# 5_-_Position2Go_PowerSupply_and_Connecto.net
KiCad netlist of a schematic drawn in Altium Designer
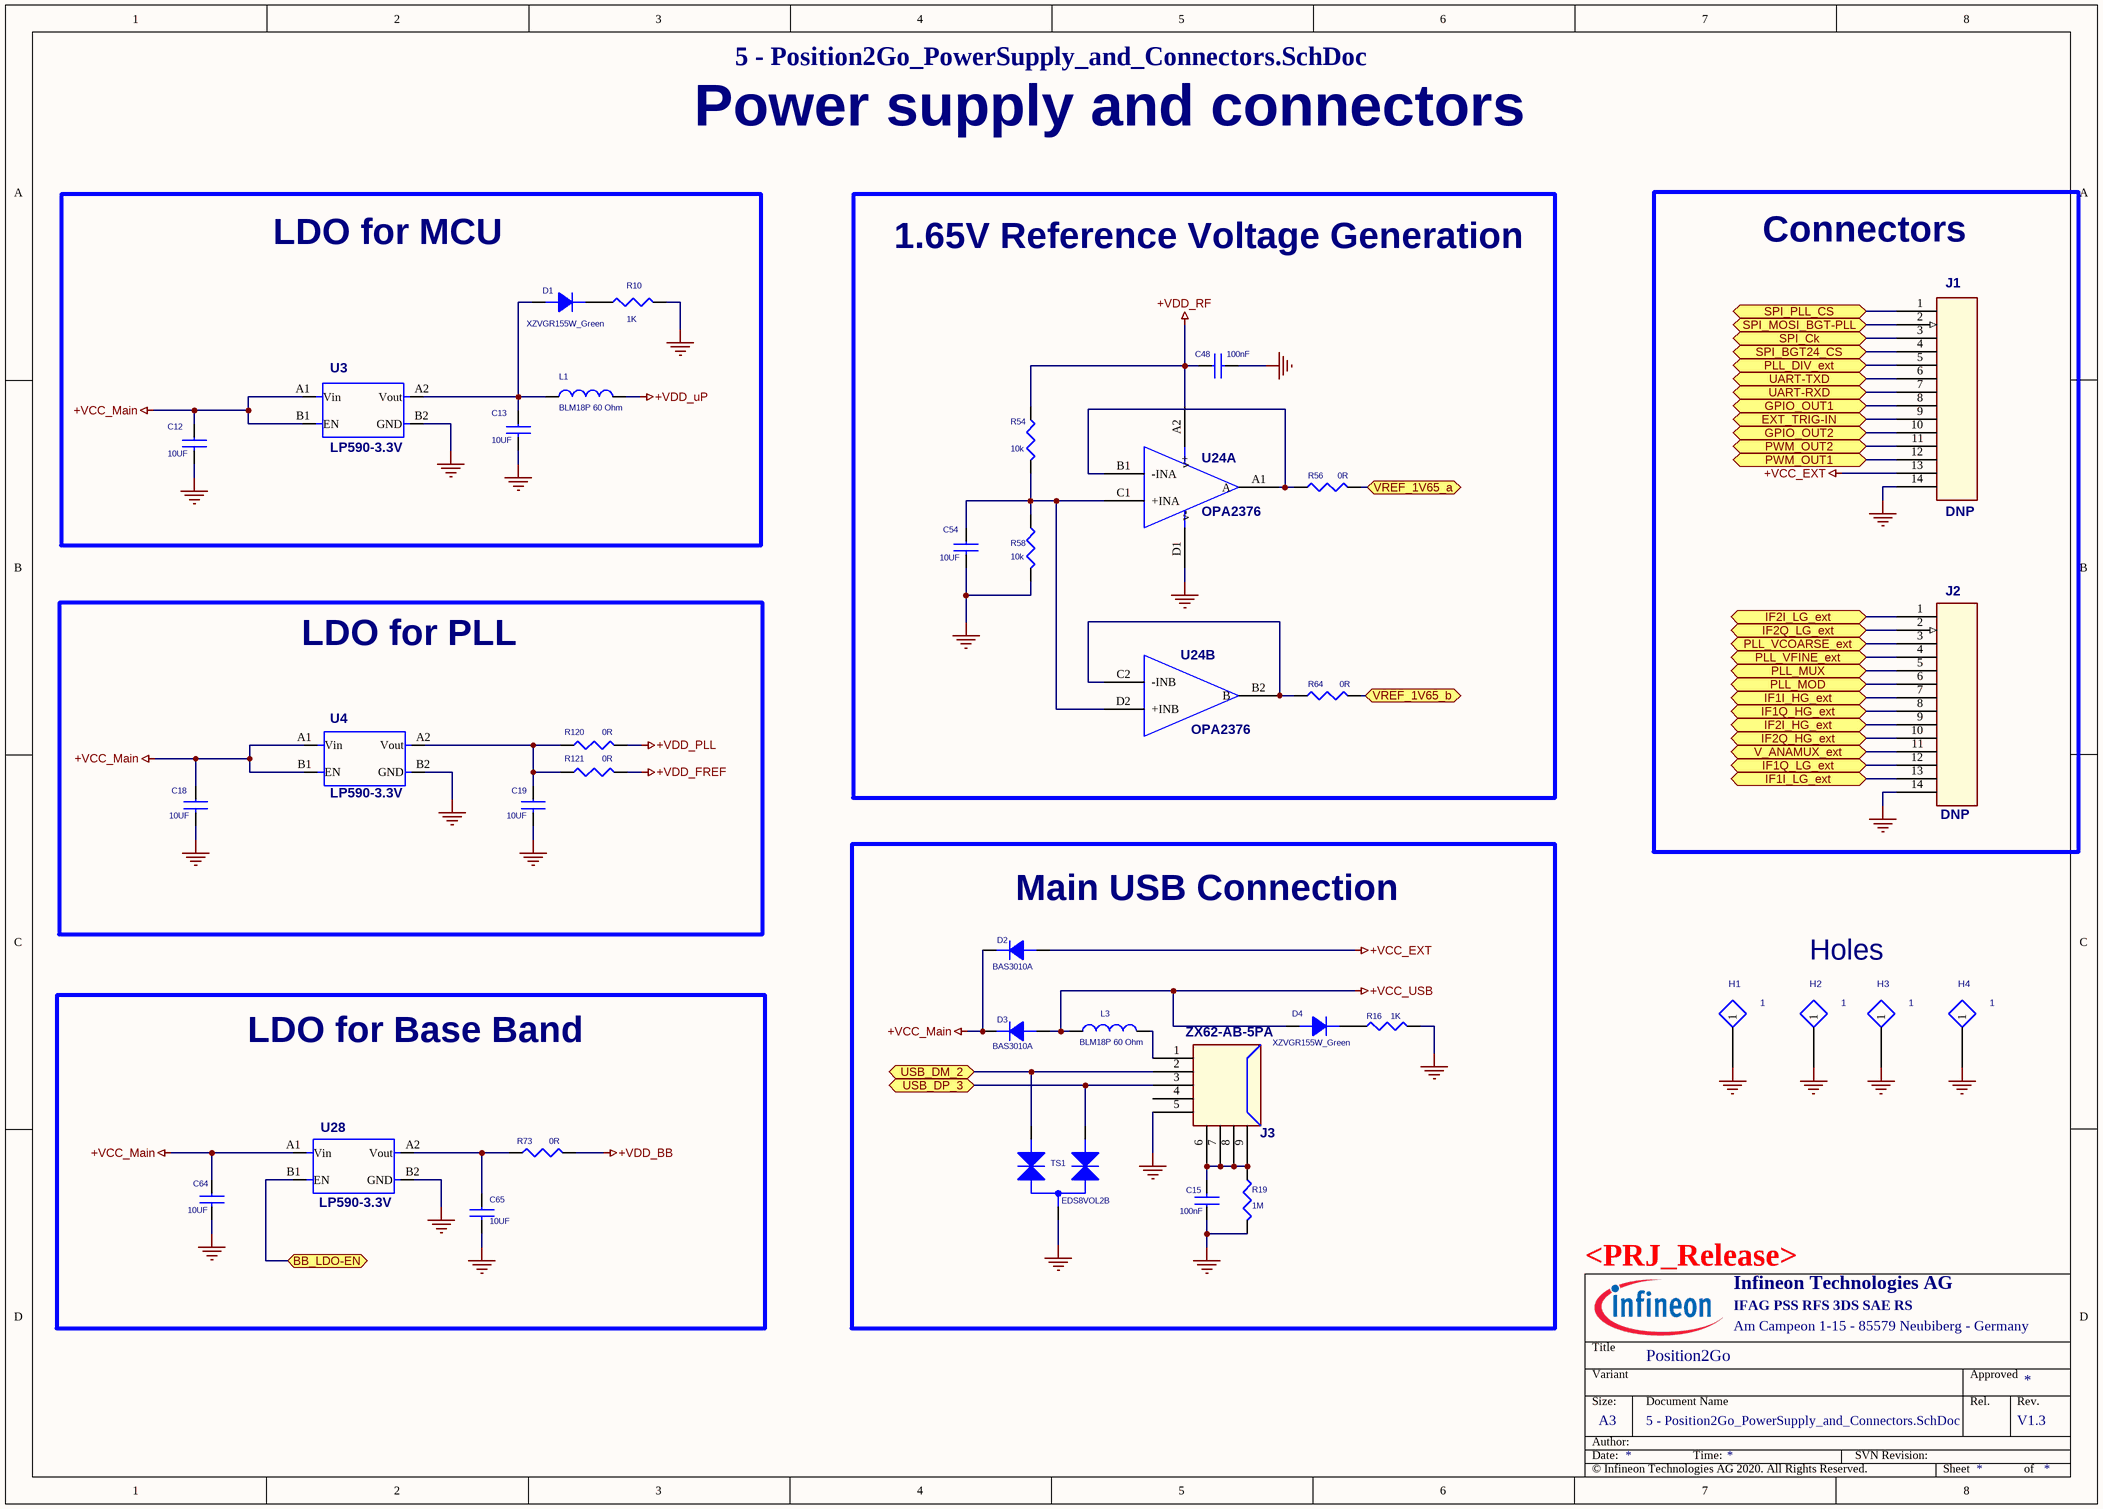
[diagram p0: 5 - Position2Go_PowerSupply_and_Connectors.SchDoc]

(export (version "E")
  (design (tool "Eeschema 10.0.6"))
  (components
    (comp (ref "C12")
      (value "10UF")
      (footprint "0402_durac")
      (fields (field (name "TOLERANCE") "20%") (field (name "VOLTAGE") "10V"))
      (libsource (lib "*") (part "10UF"))
    )
    (comp (ref "C13")
      (value "10UF")
      (footprint "0402_durac")
      (fields (field (name "TOLERANCE") "20%") (field (name "VOLTAGE") "10V"))
      (libsource (lib "*") (part "10UF"))
    )
    (comp (ref "C15")
      (value "100nF")
      (footprint "0402_durac")
      (description "100nF  ±5%  16V  X7R")
      (libsource (lib "*") (part "CAP NP"))
    )
    (comp (ref "C18")
      (value "10UF")
      (footprint "0402_durac")
      (fields (field (name "TOLERANCE") "20%") (field (name "VOLTAGE") "10V"))
      (libsource (lib "*") (part "10UF"))
    )
    (comp (ref "C19")
      (value "10UF")
      (footprint "0402_durac")
      (fields (field (name "TOLERANCE") "20%") (field (name "VOLTAGE") "10V"))
      (libsource (lib "*") (part "10UF"))
    )
    (comp (ref "C48")
      (value "100nF")
      (footprint "C_0201")
      (fields (field (name "VOLTAGE") "50V") (field (name "TOLERANCE") "5%"))
      (libsource (lib "*") (part "100nF_Dup1"))
    )
    (comp (ref "C54")
      (value "10UF")
      (footprint "0402_durac")
      (fields (field (name "TOLERANCE") "20%") (field (name "VOLTAGE") "10V"))
      (libsource (lib "*") (part "10UF"))
    )
    (comp (ref "C64")
      (value "10UF")
      (footprint "0402_durac")
      (fields (field (name "TOLERANCE") "20%") (field (name "VOLTAGE") "10V"))
      (libsource (lib "*") (part "10UF"))
    )
    (comp (ref "C65")
      (value "10UF")
      (footprint "0402_durac")
      (fields (field (name "TOLERANCE") "20%") (field (name "VOLTAGE") "10V"))
      (libsource (lib "*") (part "10UF"))
    )
    (comp (ref "D1")
      (value "XZVGR155W_Green")
      (footprint "LED_0201")
      (libsource (lib "*") (part "LED_0201_GREEN"))
    )
    (comp (ref "D2") (value "BAS3010A") (footprint "sod323") (libsource (lib "*") (part "BAS3010A")))
    (comp (ref "D3") (value "BAS3010A") (footprint "sod323") (libsource (lib "*") (part "BAS3010A")))
    (comp (ref "D4")
      (value "XZVGR155W_Green")
      (footprint "LED_0201")
      (libsource (lib "*") (part "LED_0201_GREEN"))
    )
    (comp (ref "H1") (value "1") (footprint "vite_1mm") (libsource (lib "*") (part "vite_1mm")))
    (comp (ref "H2") (value "1") (footprint "vite_1mm") (libsource (lib "*") (part "vite_1mm")))
    (comp (ref "H3") (value "1") (footprint "vite_1mm") (libsource (lib "*") (part "vite_1mm")))
    (comp (ref "H4") (value "1") (footprint "vite_1mm") (libsource (lib "*") (part "vite_1mm")))
    (comp (ref "J1")
      (value "DNP")
      (footprint "conn_14_90deg_th")
      (description "NB Not Fitted")
      (libsource (lib "*") (part "14pos_TH_90_singola_fila"))
    )
    (comp (ref "J2")
      (value "DNP")
      (footprint "conn_14_90deg_th")
      (description "NB Not Fitted")
      (libsource (lib "*") (part "14pos_TH_90_singola_fila"))
    )
    (comp (ref "J3")
      (value "ZX62-AB-5PA")
      (footprint "micro_AB_ZX62")
      (libsource (lib "*") (part "CON_MICRO_AB"))
    )
    (comp (ref "L1")
      (value "BLM18P 60 Ohm")
      (footprint "L_0603")
      (libsource (lib "*") (part "blm18 p 60 ohm"))
    )
    (comp (ref "L3")
      (value "BLM18P 60 Ohm")
      (footprint "L_0603")
      (libsource (lib "") (part "blm18 p 60 ohm_1"))
    )
    (comp (ref "R10")
      (value "1K")
      (footprint "R_0201")
      (fields (field (name "POWER") "0.063W") (field (name "TOLERANCE") "1%"))
      (libsource (lib "*") (part "1K"))
    )
    (comp (ref "R16")
      (value "1K")
      (footprint "R_0201")
      (fields (field (name "POWER") "0.063W") (field (name "TOLERANCE") "1%"))
      (libsource (lib "*") (part "1K"))
    )
    (comp (ref "R19")
      (value "1M")
      (footprint "R_0201")
      (fields (field (name "POWER") "0.063W") (field (name "TOLERANCE") "1%"))
      (libsource (lib "*") (part "1M"))
    )
    (comp (ref "R54")
      (value "10k")
      (footprint "R_0201")
      (fields (field (name "TOLERANCE") "1%") (field (name "POWER") "0.063W"))
      (libsource (lib "*") (part "10K_Dup1"))
    )
    (comp (ref "R56")
      (value "0R")
      (footprint "R_0201")
      (fields (field (name "TOLERANCE") "1%") (field (name "POWER") "0.063W"))
      (libsource (lib "*") (part "0_Dup2"))
    )
    (comp (ref "R58")
      (value "10k")
      (footprint "R_0201")
      (fields (field (name "TOLERANCE") "1%") (field (name "POWER") "0.063W"))
      (libsource (lib "*") (part "10K_Dup1"))
    )
    (comp (ref "R64")
      (value "0R")
      (footprint "R_0201")
      (fields (field (name "TOLERANCE") "1%") (field (name "POWER") "0.063W"))
      (libsource (lib "*") (part "0_Dup2"))
    )
    (comp (ref "R73")
      (value "0R")
      (footprint "0603")
      (description "0R 0603")
      (fields (field (name "TOLERANCE") "1%") (field (name "POWER") "0.125W"))
      (libsource (lib "*") (part "0"))
    )
    (comp (ref "R120")
      (value "0R")
      (footprint "0603")
      (description "0R 0603")
      (fields (field (name "TOLERANCE") "1%") (field (name "POWER") "0.125W"))
      (libsource (lib "*") (part "0"))
    )
    (comp (ref "R121")
      (value "0R")
      (footprint "0603")
      (description "0R 0603")
      (fields (field (name "TOLERANCE") "1%") (field (name "POWER") "0.125W"))
      (libsource (lib "*") (part "0"))
    )
    (comp (ref "TS1") (value "EDS8VOL2B") (footprint "ESD8VOL2B") (libsource (lib "*") (part "ESD8VOL2B")))
    (comp (ref "U3") (value "LP590-3.3V") (footprint "YKE4") (libsource (lib "*") (part "LP5907_BGA")))
    (comp (ref "U4") (value "LP590-3.3V") (footprint "YKE4") (libsource (lib "*") (part "LP5907_BGA")))
    (comp (ref "U24")
      (value "OPA2376")
      (footprint "OPA2376_DSBGA")
      (libsource (lib "*") (part "OPA2376_DSBGA"))
    )
    (comp (ref "U28") (value "LP590-3.3V") (footprint "YKE4") (libsource (lib "*") (part "LP5907_BGA")))
  )
  (nets
    (net (code "1") (name "+VCC_EXT") (class "Default")
      (node (ref "D2") (pin "2") (pinfunction "A_2") (pintype "passive"))
      (node (ref "J1") (pin "13") (pinfunction "13_13") (pintype "passive"))
    )
    (net (code "2") (name "+VCC_Main") (class "Default")
      (node (ref "C12") (pin "1") (pinfunction "1_1") (pintype "passive"))
      (node (ref "C18") (pin "1") (pinfunction "1_1") (pintype "passive"))
      (node (ref "C64") (pin "1") (pinfunction "1_1") (pintype "passive"))
      (node (ref "D2") (pin "1") (pinfunction "K_1") (pintype "passive"))
      (node (ref "D3") (pin "1") (pinfunction "K_1") (pintype "passive"))
      (node (ref "U28") (pin "A1") (pinfunction "Vin_A1") (pintype "passive"))
      (node (ref "U3") (pin "A1") (pinfunction "Vin_A1") (pintype "passive"))
      (node (ref "U3") (pin "B1") (pinfunction "EN_B1") (pintype "passive"))
      (node (ref "U4") (pin "A1") (pinfunction "Vin_A1") (pintype "passive"))
      (node (ref "U4") (pin "B1") (pinfunction "EN_B1") (pintype "passive"))
    )
    (net (code "3") (name "+VCC_USB") (class "Default")
      (node (ref "D3") (pin "2") (pinfunction "A_2") (pintype "passive"))
      (node (ref "D4") (pin "2") (pinfunction "A_2") (pintype "passive"))
      (node (ref "L3") (pin "2") (pinfunction "2_2") (pintype "passive"))
    )
    (net (code "4") (name "+VDD_BB") (class "Default")
      (node (ref "R73") (pin "1") (pinfunction "1_1") (pintype "passive"))
    )
    (net (code "5") (name "+VDD_FREF") (class "Default")
      (node (ref "R121") (pin "2") (pinfunction "2_2") (pintype "passive"))
    )
    (net (code "6") (name "+VDD_PLL") (class "Default")
      (node (ref "R120") (pin "2") (pinfunction "2_2") (pintype "passive"))
    )
    (net (code "7") (name "+VDD_RF") (class "Default")
      (node (ref "C48") (pin "1") (pinfunction "1_1") (pintype "passive"))
      (node (ref "R54") (pin "1") (pinfunction "1_1") (pintype "passive"))
      (node (ref "U24") (pin "A2") (pinfunction "v+_A2") (pintype "power_in"))
    )
    (net (code "8") (name "+VDD_uP") (class "Default")
      (node (ref "L1") (pin "2") (pinfunction "2_2") (pintype "passive"))
    )
    (net (code "9") (name "/BB_LDO-EN") (class "Default")
      (node (ref "U28") (pin "B1") (pinfunction "EN_B1") (pintype "passive"))
    )
    (net (code "10") (name "/EXT_TRIG-IN") (class "Default")
      (node (ref "J1") (pin "9") (pinfunction "9_9") (pintype "passive"))
    )
    (net (code "11") (name "/GPIO_OUT1") (class "Default")
      (node (ref "J1") (pin "8") (pinfunction "8_8") (pintype "passive"))
    )
    (net (code "12") (name "/GPIO_OUT2") (class "Default")
      (node (ref "J1") (pin "10") (pinfunction "10_10") (pintype "passive"))
    )
    (net (code "13") (name "/IF1I_HG_ext") (class "Default")
      (node (ref "J2") (pin "7") (pinfunction "7_7") (pintype "passive"))
    )
    (net (code "14") (name "/IF1I_LG_ext") (class "Default")
      (node (ref "J2") (pin "13") (pinfunction "13_13") (pintype "passive"))
    )
    (net (code "15") (name "/IF1Q_HG_ext") (class "Default")
      (node (ref "J2") (pin "8") (pinfunction "8_8") (pintype "passive"))
    )
    (net (code "16") (name "/IF1Q_LG_ext") (class "Default")
      (node (ref "J2") (pin "12") (pinfunction "12_12") (pintype "passive"))
    )
    (net (code "17") (name "/IF2I_HG_ext") (class "Default")
      (node (ref "J2") (pin "9") (pinfunction "9_9") (pintype "passive"))
    )
    (net (code "18") (name "/IF2I_LG_ext") (class "Default")
      (node (ref "J2") (pin "1") (pinfunction "1_1") (pintype "passive"))
    )
    (net (code "19") (name "/IF2Q_HG_ext") (class "Default")
      (node (ref "J2") (pin "10") (pinfunction "10_10") (pintype "passive"))
    )
    (net (code "20") (name "/IF2Q_LG_ext") (class "Default")
      (node (ref "J2") (pin "2") (pinfunction "2_2") (pintype "input"))
    )
    (net (code "21") (name "/PLL_DIV_ext") (class "Default")
      (node (ref "J1") (pin "5") (pinfunction "5_5") (pintype "passive"))
    )
    (net (code "22") (name "/PLL_MOD") (class "Default")
      (node (ref "J2") (pin "6") (pinfunction "6_6") (pintype "passive"))
    )
    (net (code "23") (name "/PLL_MUX") (class "Default")
      (node (ref "J2") (pin "5") (pinfunction "5_5") (pintype "passive"))
    )
    (net (code "24") (name "/PLL_VCOARSE_ext") (class "Default")
      (node (ref "J2") (pin "3") (pinfunction "3_3") (pintype "passive"))
    )
    (net (code "25") (name "/PLL_VFINE_ext") (class "Default")
      (node (ref "J2") (pin "4") (pinfunction "4_4") (pintype "passive"))
    )
    (net (code "26") (name "/PWM_OUT1") (class "Default")
      (node (ref "J1") (pin "12") (pinfunction "12_12") (pintype "passive"))
    )
    (net (code "27") (name "/PWM_OUT2") (class "Default")
      (node (ref "J1") (pin "11") (pinfunction "11_11") (pintype "passive"))
    )
    (net (code "28") (name "/SPI_BGT24_CS") (class "Default")
      (node (ref "J1") (pin "4") (pinfunction "4_4") (pintype "passive"))
    )
    (net (code "29") (name "/SPI_Ck") (class "Default")
      (node (ref "J1") (pin "3") (pinfunction "3_3") (pintype "passive"))
    )
    (net (code "30") (name "/SPI_MOSI_BGT-PLL") (class "Default")
      (node (ref "J1") (pin "2") (pinfunction "2_2") (pintype "input"))
    )
    (net (code "31") (name "/SPI_PLL_CS") (class "Default")
      (node (ref "J1") (pin "1") (pinfunction "1_1") (pintype "passive"))
    )
    (net (code "32") (name "/UART-RXD") (class "Default")
      (node (ref "J1") (pin "7") (pinfunction "7_7") (pintype "passive"))
    )
    (net (code "33") (name "/UART-TXD") (class "Default")
      (node (ref "J1") (pin "6") (pinfunction "6_6") (pintype "passive"))
    )
    (net (code "34") (name "/USB_DM_2") (class "Default")
      (node (ref "J3") (pin "2") (pinfunction "2_2") (pintype "passive"))
      (node (ref "TS1") (pin "1") (pinfunction "1_1") (pintype "passive"))
    )
    (net (code "35") (name "/USB_DP_3") (class "Default")
      (node (ref "J3") (pin "3") (pinfunction "3_3") (pintype "passive"))
      (node (ref "TS1") (pin "2") (pinfunction "2_2") (pintype "passive"))
    )
    (net (code "36") (name "/VREF_1V65_a") (class "Default")
      (node (ref "R56") (pin "2") (pinfunction "2_2") (pintype "passive"))
    )
    (net (code "37") (name "/VREF_1V65_b") (class "Default")
      (node (ref "R64") (pin "2") (pinfunction "2_2") (pintype "passive"))
    )
    (net (code "38") (name "/V_ANAMUX_ext") (class "Default")
      (node (ref "J2") (pin "11") (pinfunction "11_11") (pintype "passive"))
    )
    (net (code "39") (name "GND_POWER") (class "Default")
      (node (ref "C12") (pin "2") (pinfunction "2_2") (pintype "passive"))
      (node (ref "C13") (pin "2") (pinfunction "2_2") (pintype "passive"))
      (node (ref "C15") (pin "1") (pinfunction "1_1") (pintype "passive"))
      (node (ref "C18") (pin "2") (pinfunction "2_2") (pintype "passive"))
      (node (ref "C19") (pin "2") (pinfunction "2_2") (pintype "passive"))
      (node (ref "C48") (pin "2") (pinfunction "2_2") (pintype "passive"))
      (node (ref "C54") (pin "2") (pinfunction "2_2") (pintype "passive"))
      (node (ref "C64") (pin "2") (pinfunction "2_2") (pintype "passive"))
      (node (ref "C65") (pin "2") (pinfunction "2_2") (pintype "passive"))
      (node (ref "H1") (pin "1") (pinfunction "1_1") (pintype "passive"))
      (node (ref "H2") (pin "1") (pinfunction "1_1") (pintype "passive"))
      (node (ref "H3") (pin "1") (pinfunction "1_1") (pintype "passive"))
      (node (ref "H4") (pin "1") (pinfunction "1_1") (pintype "passive"))
      (node (ref "J1") (pin "14") (pinfunction "14_14") (pintype "passive"))
      (node (ref "J2") (pin "14") (pinfunction "14_14") (pintype "passive"))
      (node (ref "J3") (pin "5") (pinfunction "5_5") (pintype "passive"))
      (node (ref "R10") (pin "1") (pinfunction "1_1") (pintype "passive"))
      (node (ref "R16") (pin "1") (pinfunction "1_1") (pintype "passive"))
      (node (ref "R19") (pin "2") (pinfunction "2_2") (pintype "passive"))
      (node (ref "R58") (pin "2") (pinfunction "2_2") (pintype "passive"))
      (node (ref "TS1") (pin "3") (pinfunction "3_3") (pintype "passive"))
      (node (ref "U24") (pin "D1") (pinfunction "v-_D1") (pintype "power_in"))
      (node (ref "U28") (pin "B2") (pinfunction "GND_B2") (pintype "passive"))
      (node (ref "U3") (pin "B2") (pinfunction "GND_B2") (pintype "passive"))
      (node (ref "U4") (pin "B2") (pinfunction "GND_B2") (pintype "passive"))
    )
    (net (code "40") (name "Net-(D1-A)") (class "Default")
      (node (ref "C13") (pin "1") (pinfunction "1_1") (pintype "passive"))
      (node (ref "D1") (pin "2") (pinfunction "A_2") (pintype "passive"))
      (node (ref "L1") (pin "1") (pinfunction "1_1") (pintype "passive"))
      (node (ref "U3") (pin "A2") (pinfunction "Vout_A2") (pintype "passive"))
    )
    (net (code "41") (name "Net-(D1-K)") (class "Default")
      (node (ref "D1") (pin "1") (pinfunction "K_1") (pintype "passive"))
      (node (ref "R10") (pin "2") (pinfunction "2_2") (pintype "passive"))
    )
    (net (code "42") (name "Net-(D4-K)") (class "Default")
      (node (ref "D4") (pin "1") (pinfunction "K_1") (pintype "passive"))
      (node (ref "R16") (pin "2") (pinfunction "2_2") (pintype "passive"))
    )
    (net (code "43") (name "Net-(J3-GNd)") (class "Default")
      (node (ref "C15") (pin "2") (pinfunction "2_2") (pintype "passive"))
      (node (ref "J3") (pin "6") (pinfunction "GND_6") (pintype "power_in"))
      (node (ref "J3") (pin "7") (pinfunction "GND_7") (pintype "power_in"))
      (node (ref "J3") (pin "8") (pinfunction "GND_8") (pintype "power_in"))
      (node (ref "J3") (pin "9") (pinfunction "GNd_9") (pintype "power_in"))
      (node (ref "R19") (pin "1") (pinfunction "1_1") (pintype "passive"))
    )
    (net (code "44") (name "Net-(J3-Pad1)") (class "Default")
      (node (ref "J3") (pin "1") (pinfunction "1_1") (pintype "passive"))
      (node (ref "L3") (pin "1") (pinfunction "1_1") (pintype "passive"))
    )
    (net (code "45") (name "Net-(U4-Vout)") (class "Default")
      (node (ref "C19") (pin "1") (pinfunction "1_1") (pintype "passive"))
      (node (ref "R120") (pin "1") (pinfunction "1_1") (pintype "passive"))
      (node (ref "R121") (pin "1") (pinfunction "1_1") (pintype "passive"))
      (node (ref "U4") (pin "A2") (pinfunction "Vout_A2") (pintype "passive"))
    )
    (net (code "46") (name "Net-(U24A-+INA)") (class "Default")
      (node (ref "C54") (pin "1") (pinfunction "1_1") (pintype "passive"))
      (node (ref "R54") (pin "2") (pinfunction "2_2") (pintype "passive"))
      (node (ref "R58") (pin "1") (pinfunction "1_1") (pintype "passive"))
      (node (ref "U24") (pin "C1") (pinfunction "+INA_C1") (pintype "passive"))
      (node (ref "U24") (pin "D2") (pinfunction "+INB_D2") (pintype "passive"))
    )
    (net (code "47") (name "Net-(U24A--INA)") (class "Default")
      (node (ref "R56") (pin "1") (pinfunction "1_1") (pintype "passive"))
      (node (ref "U24") (pin "A1") (pinfunction "A_A1") (pintype "passive"))
      (node (ref "U24") (pin "B1") (pinfunction "-INA_B1") (pintype "passive"))
    )
    (net (code "48") (name "Net-(U24B--INB)") (class "Default")
      (node (ref "R64") (pin "1") (pinfunction "1_1") (pintype "passive"))
      (node (ref "U24") (pin "B2") (pinfunction "B_B2") (pintype "passive"))
      (node (ref "U24") (pin "C2") (pinfunction "-INB_C2") (pintype "passive"))
    )
    (net (code "49") (name "Net-(U28-Vout)") (class "Default")
      (node (ref "C65") (pin "1") (pinfunction "1_1") (pintype "passive"))
      (node (ref "R73") (pin "2") (pinfunction "2_2") (pintype "passive"))
      (node (ref "U28") (pin "A2") (pinfunction "Vout_A2") (pintype "passive"))
    )
    (net (code "50") (name "unconnected-(J3-Pad4)") (class "Default")
      (node (ref "J3") (pin "4") (pinfunction "4_4") (pintype "passive"))
    )
  )
)
